# zdroj.net
KiCad netlist of a schematic drawn in EAGLE
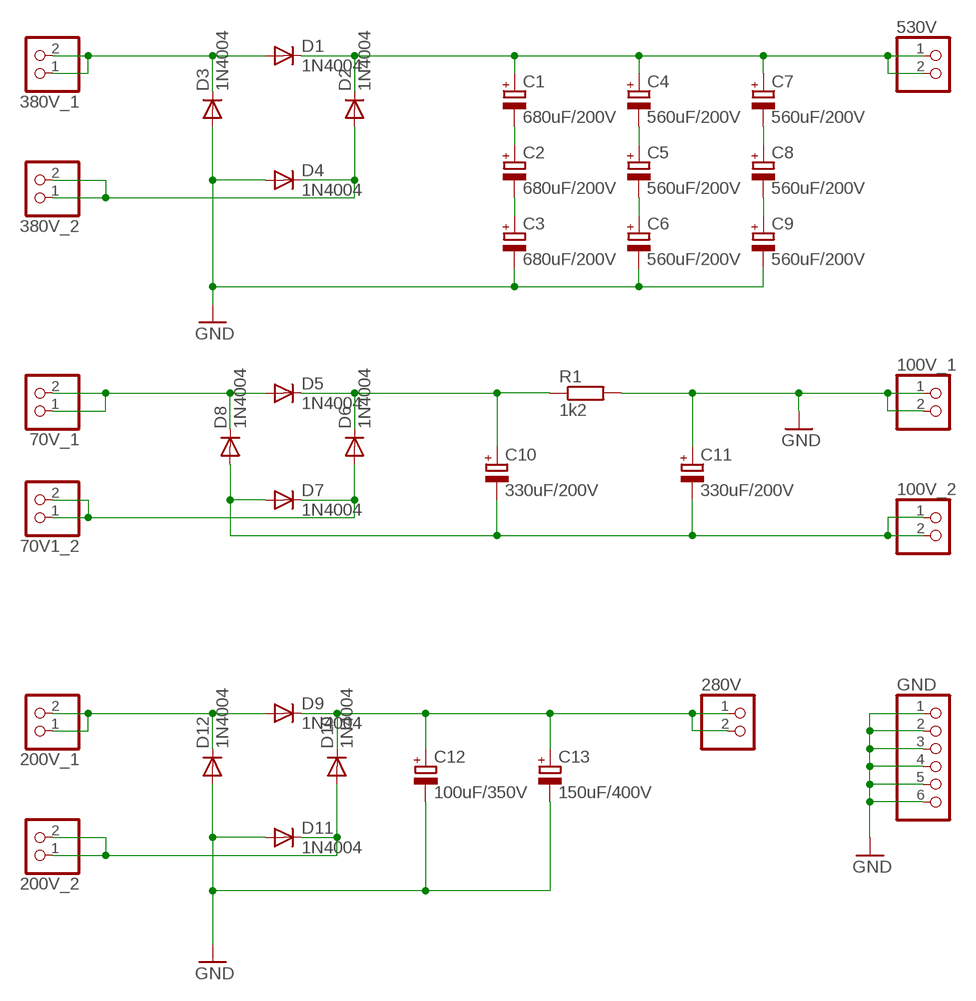
[diagram p0: schematic, sheet 1]

(export (version "E")
  (design (tool "Eeschema 10.0.6"))
  (components
    (comp (ref "70V1_2")
      (value "PINHD-1X2")
      (footprint "eagle-import:1X02")
      (libsource (lib "eagle-import") (part "PINHD-1X2"))
    )
    (comp (ref "70V_1")
      (value "PINHD-1X2")
      (footprint "eagle-import:1X02")
      (libsource (lib "eagle-import") (part "PINHD-1X2"))
    )
    (comp (ref "100V_1")
      (value "PINHD-1X2")
      (footprint "eagle-import:1X02")
      (libsource (lib "eagle-import") (part "PINHD-1X2"))
    )
    (comp (ref "100V_2")
      (value "PINHD-1X2")
      (footprint "eagle-import:1X02")
      (libsource (lib "eagle-import") (part "PINHD-1X2"))
    )
    (comp (ref "200V_1")
      (value "PINHD-1X2")
      (footprint "eagle-import:1X02")
      (libsource (lib "eagle-import") (part "PINHD-1X2"))
    )
    (comp (ref "200V_2")
      (value "PINHD-1X2")
      (footprint "eagle-import:1X02")
      (libsource (lib "eagle-import") (part "PINHD-1X2"))
    )
    (comp (ref "280V")
      (value "PINHD-1X2")
      (footprint "eagle-import:1X02")
      (libsource (lib "eagle-import") (part "PINHD-1X2"))
    )
    (comp (ref "380V_1")
      (value "PINHD-1X2")
      (footprint "eagle-import:1X02")
      (libsource (lib "eagle-import") (part "PINHD-1X2"))
    )
    (comp (ref "380V_2")
      (value "PINHD-1X2")
      (footprint "eagle-import:1X02")
      (libsource (lib "eagle-import") (part "PINHD-1X2"))
    )
    (comp (ref "530V")
      (value "PINHD-1X2")
      (footprint "eagle-import:1X02")
      (libsource (lib "eagle-import") (part "PINHD-1X2"))
    )
    (comp (ref "C1")
      (value "680uF/200V")
      (footprint "eagle-import:EB22,5D")
      (libsource (lib "eagle-import") (part "CPOL-EUE10-22.5"))
    )
    (comp (ref "C2")
      (value "680uF/200V")
      (footprint "eagle-import:EB22,5D")
      (libsource (lib "eagle-import") (part "CPOL-EUE10-22.5"))
    )
    (comp (ref "C3")
      (value "680uF/200V")
      (footprint "eagle-import:EB22,5D")
      (libsource (lib "eagle-import") (part "CPOL-EUE10-22.5"))
    )
    (comp (ref "C4")
      (value "560uF/200V")
      (footprint "eagle-import:EB22,5D")
      (libsource (lib "eagle-import") (part "CPOL-EUE10-22.5"))
    )
    (comp (ref "C5")
      (value "560uF/200V")
      (footprint "eagle-import:EB22,5D")
      (libsource (lib "eagle-import") (part "CPOL-EUE10-22.5"))
    )
    (comp (ref "C6")
      (value "560uF/200V")
      (footprint "eagle-import:EB22,5D")
      (libsource (lib "eagle-import") (part "CPOL-EUE10-22.5"))
    )
    (comp (ref "C7")
      (value "560uF/200V")
      (footprint "eagle-import:EB22,5D")
      (libsource (lib "eagle-import") (part "CPOL-EUE10-22.5"))
    )
    (comp (ref "C8")
      (value "560uF/200V")
      (footprint "eagle-import:EB22,5D")
      (libsource (lib "eagle-import") (part "CPOL-EUE10-22.5"))
    )
    (comp (ref "C9")
      (value "560uF/200V")
      (footprint "eagle-import:EB22,5D")
      (libsource (lib "eagle-import") (part "CPOL-EUE10-22.5"))
    )
    (comp (ref "C10")
      (value "330uF/200V")
      (footprint "eagle-import:EB22,5D")
      (libsource (lib "eagle-import") (part "CPOL-EUE10-22.5"))
    )
    (comp (ref "C11")
      (value "330uF/200V")
      (footprint "eagle-import:EB22,5D")
      (libsource (lib "eagle-import") (part "CPOL-EUE10-22.5"))
    )
    (comp (ref "C12")
      (value "100uF/350V")
      (footprint "eagle-import:E7,5-18")
      (libsource (lib "eagle-import") (part "CPOL-EUE7.5-18"))
    )
    (comp (ref "C13")
      (value "150uF/400V")
      (footprint "eagle-import:E7,5-18")
      (libsource (lib "eagle-import") (part "CPOL-EUE7.5-18"))
    )
    (comp (ref "D1")
      (value "1N4004")
      (footprint "eagle-import:DO41-10")
      (libsource (lib "eagle-import") (part "1N4004"))
    )
    (comp (ref "D2")
      (value "1N4004")
      (footprint "eagle-import:DO41-10")
      (libsource (lib "eagle-import") (part "1N4004"))
    )
    (comp (ref "D3")
      (value "1N4004")
      (footprint "eagle-import:DO41-10")
      (libsource (lib "eagle-import") (part "1N4004"))
    )
    (comp (ref "D4")
      (value "1N4004")
      (footprint "eagle-import:DO41-10")
      (libsource (lib "eagle-import") (part "1N4004"))
    )
    (comp (ref "D5")
      (value "1N4004")
      (footprint "eagle-import:DO41-10")
      (libsource (lib "eagle-import") (part "1N4004"))
    )
    (comp (ref "D6")
      (value "1N4004")
      (footprint "eagle-import:DO41-10")
      (libsource (lib "eagle-import") (part "1N4004"))
    )
    (comp (ref "D7")
      (value "1N4004")
      (footprint "eagle-import:DO41-10")
      (libsource (lib "eagle-import") (part "1N4004"))
    )
    (comp (ref "D8")
      (value "1N4004")
      (footprint "eagle-import:DO41-10")
      (libsource (lib "eagle-import") (part "1N4004"))
    )
    (comp (ref "D9")
      (value "1N4004")
      (footprint "eagle-import:DO41-10")
      (libsource (lib "eagle-import") (part "1N4004"))
    )
    (comp (ref "D10")
      (value "1N4004")
      (footprint "eagle-import:DO41-10")
      (libsource (lib "eagle-import") (part "1N4004"))
    )
    (comp (ref "D11")
      (value "1N4004")
      (footprint "eagle-import:DO41-10")
      (libsource (lib "eagle-import") (part "1N4004"))
    )
    (comp (ref "D12")
      (value "1N4004")
      (footprint "eagle-import:DO41-10")
      (libsource (lib "eagle-import") (part "1N4004"))
    )
    (comp (ref "GND")
      (value "PINHD-1X6")
      (footprint "eagle-import:1X06")
      (libsource (lib "eagle-import") (part "PINHD-1X6"))
    )
    (comp (ref "R1")
      (value "1k2")
      (footprint "eagle-import:0309_12")
      (libsource (lib "eagle-import") (part "R-EU_0309/12"))
    )
  )
  (nets
    (net (code "1") (name "GND") (class "Default")
      (node (ref "100V_1") (pin "1") (pinfunction "1_1") (pintype "passive"))
      (node (ref "100V_1") (pin "2") (pinfunction "2_2") (pintype "passive"))
      (node (ref "C11") (pin "+") (pinfunction "+_+") (pintype "passive"))
      (node (ref "C12") (pin "-") (pinfunction "-_-") (pintype "passive"))
      (node (ref "C13") (pin "-") (pinfunction "-_-") (pintype "passive"))
      (node (ref "C3") (pin "-") (pinfunction "-_-") (pintype "passive"))
      (node (ref "C6") (pin "-") (pinfunction "-_-") (pintype "passive"))
      (node (ref "C9") (pin "-") (pinfunction "-_-") (pintype "passive"))
      (node (ref "D11") (pin "A") (pinfunction "A_A") (pintype "passive"))
      (node (ref "D12") (pin "A") (pinfunction "A_A") (pintype "passive"))
      (node (ref "D3") (pin "A") (pinfunction "A_A") (pintype "passive"))
      (node (ref "D4") (pin "A") (pinfunction "A_A") (pintype "passive"))
      (node (ref "GND") (pin "1") (pinfunction "1_1") (pintype "passive"))
      (node (ref "GND") (pin "2") (pinfunction "2_2") (pintype "passive"))
      (node (ref "GND") (pin "3") (pinfunction "3_3") (pintype "passive"))
      (node (ref "GND") (pin "4") (pinfunction "4_4") (pintype "passive"))
      (node (ref "GND") (pin "5") (pinfunction "5_5") (pintype "passive"))
      (node (ref "GND") (pin "6") (pinfunction "6_6") (pintype "passive"))
      (node (ref "R1") (pin "2") (pinfunction "2_2") (pintype "passive"))
    )
    (net (code "2") (name "Net-(70V1_2-Pad1)") (class "Default")
      (node (ref "70V1_2") (pin "1") (pinfunction "1_1") (pintype "passive"))
      (node (ref "70V1_2") (pin "2") (pinfunction "2_2") (pintype "passive"))
      (node (ref "D6") (pin "A") (pinfunction "A_A") (pintype "passive"))
      (node (ref "D7") (pin "C") (pinfunction "C_C") (pintype "passive"))
    )
    (net (code "3") (name "Net-(70V_1-Pad1)") (class "Default")
      (node (ref "70V_1") (pin "1") (pinfunction "1_1") (pintype "passive"))
      (node (ref "70V_1") (pin "2") (pinfunction "2_2") (pintype "passive"))
      (node (ref "D5") (pin "A") (pinfunction "A_A") (pintype "passive"))
      (node (ref "D8") (pin "C") (pinfunction "C_C") (pintype "passive"))
    )
    (net (code "4") (name "Net-(100V_2-Pad1)") (class "Default")
      (node (ref "100V_2") (pin "1") (pinfunction "1_1") (pintype "passive"))
      (node (ref "100V_2") (pin "2") (pinfunction "2_2") (pintype "passive"))
      (node (ref "C10") (pin "-") (pinfunction "-_-") (pintype "passive"))
      (node (ref "C11") (pin "-") (pinfunction "-_-") (pintype "passive"))
      (node (ref "D7") (pin "A") (pinfunction "A_A") (pintype "passive"))
      (node (ref "D8") (pin "A") (pinfunction "A_A") (pintype "passive"))
    )
    (net (code "5") (name "Net-(200V_1-Pad1)") (class "Default")
      (node (ref "200V_1") (pin "1") (pinfunction "1_1") (pintype "passive"))
      (node (ref "200V_1") (pin "2") (pinfunction "2_2") (pintype "passive"))
      (node (ref "D12") (pin "C") (pinfunction "C_C") (pintype "passive"))
      (node (ref "D9") (pin "A") (pinfunction "A_A") (pintype "passive"))
    )
    (net (code "6") (name "Net-(200V_2-Pad1)") (class "Default")
      (node (ref "200V_2") (pin "1") (pinfunction "1_1") (pintype "passive"))
      (node (ref "200V_2") (pin "2") (pinfunction "2_2") (pintype "passive"))
      (node (ref "D10") (pin "A") (pinfunction "A_A") (pintype "passive"))
      (node (ref "D11") (pin "C") (pinfunction "C_C") (pintype "passive"))
    )
    (net (code "7") (name "Net-(280V-Pad1)") (class "Default")
      (node (ref "280V") (pin "1") (pinfunction "1_1") (pintype "passive"))
      (node (ref "280V") (pin "2") (pinfunction "2_2") (pintype "passive"))
      (node (ref "C12") (pin "+") (pinfunction "+_+") (pintype "passive"))
      (node (ref "C13") (pin "+") (pinfunction "+_+") (pintype "passive"))
      (node (ref "D10") (pin "C") (pinfunction "C_C") (pintype "passive"))
      (node (ref "D9") (pin "C") (pinfunction "C_C") (pintype "passive"))
    )
    (net (code "8") (name "Net-(380V_1-Pad1)") (class "Default")
      (node (ref "380V_1") (pin "1") (pinfunction "1_1") (pintype "passive"))
      (node (ref "380V_1") (pin "2") (pinfunction "2_2") (pintype "passive"))
      (node (ref "D1") (pin "A") (pinfunction "A_A") (pintype "passive"))
      (node (ref "D3") (pin "C") (pinfunction "C_C") (pintype "passive"))
    )
    (net (code "9") (name "Net-(380V_2-Pad1)") (class "Default")
      (node (ref "380V_2") (pin "1") (pinfunction "1_1") (pintype "passive"))
      (node (ref "380V_2") (pin "2") (pinfunction "2_2") (pintype "passive"))
      (node (ref "D2") (pin "A") (pinfunction "A_A") (pintype "passive"))
      (node (ref "D4") (pin "C") (pinfunction "C_C") (pintype "passive"))
    )
    (net (code "10") (name "Net-(530V-Pad1)") (class "Default")
      (node (ref "530V") (pin "1") (pinfunction "1_1") (pintype "passive"))
      (node (ref "530V") (pin "2") (pinfunction "2_2") (pintype "passive"))
      (node (ref "C1") (pin "+") (pinfunction "+_+") (pintype "passive"))
      (node (ref "C4") (pin "+") (pinfunction "+_+") (pintype "passive"))
      (node (ref "C7") (pin "+") (pinfunction "+_+") (pintype "passive"))
      (node (ref "D1") (pin "C") (pinfunction "C_C") (pintype "passive"))
      (node (ref "D2") (pin "C") (pinfunction "C_C") (pintype "passive"))
    )
    (net (code "11") (name "Net-(C1-Pad-)") (class "Default")
      (node (ref "C1") (pin "-") (pinfunction "-_-") (pintype "passive"))
      (node (ref "C2") (pin "+") (pinfunction "+_+") (pintype "passive"))
    )
    (net (code "12") (name "Net-(C2-Pad-)") (class "Default")
      (node (ref "C2") (pin "-") (pinfunction "-_-") (pintype "passive"))
      (node (ref "C3") (pin "+") (pinfunction "+_+") (pintype "passive"))
    )
    (net (code "13") (name "Net-(C4-Pad-)") (class "Default")
      (node (ref "C4") (pin "-") (pinfunction "-_-") (pintype "passive"))
      (node (ref "C5") (pin "+") (pinfunction "+_+") (pintype "passive"))
    )
    (net (code "14") (name "Net-(C5-Pad-)") (class "Default")
      (node (ref "C5") (pin "-") (pinfunction "-_-") (pintype "passive"))
      (node (ref "C6") (pin "+") (pinfunction "+_+") (pintype "passive"))
    )
    (net (code "15") (name "Net-(C7-Pad-)") (class "Default")
      (node (ref "C7") (pin "-") (pinfunction "-_-") (pintype "passive"))
      (node (ref "C8") (pin "+") (pinfunction "+_+") (pintype "passive"))
    )
    (net (code "16") (name "Net-(C8-Pad-)") (class "Default")
      (node (ref "C8") (pin "-") (pinfunction "-_-") (pintype "passive"))
      (node (ref "C9") (pin "+") (pinfunction "+_+") (pintype "passive"))
    )
    (net (code "17") (name "Net-(C10-Pad+)") (class "Default")
      (node (ref "C10") (pin "+") (pinfunction "+_+") (pintype "passive"))
      (node (ref "D5") (pin "C") (pinfunction "C_C") (pintype "passive"))
      (node (ref "D6") (pin "C") (pinfunction "C_C") (pintype "passive"))
      (node (ref "R1") (pin "1") (pinfunction "1_1") (pintype "passive"))
    )
  )
)
